# BUCK.net
KiCad netlist of a schematic drawn in Altium Designer
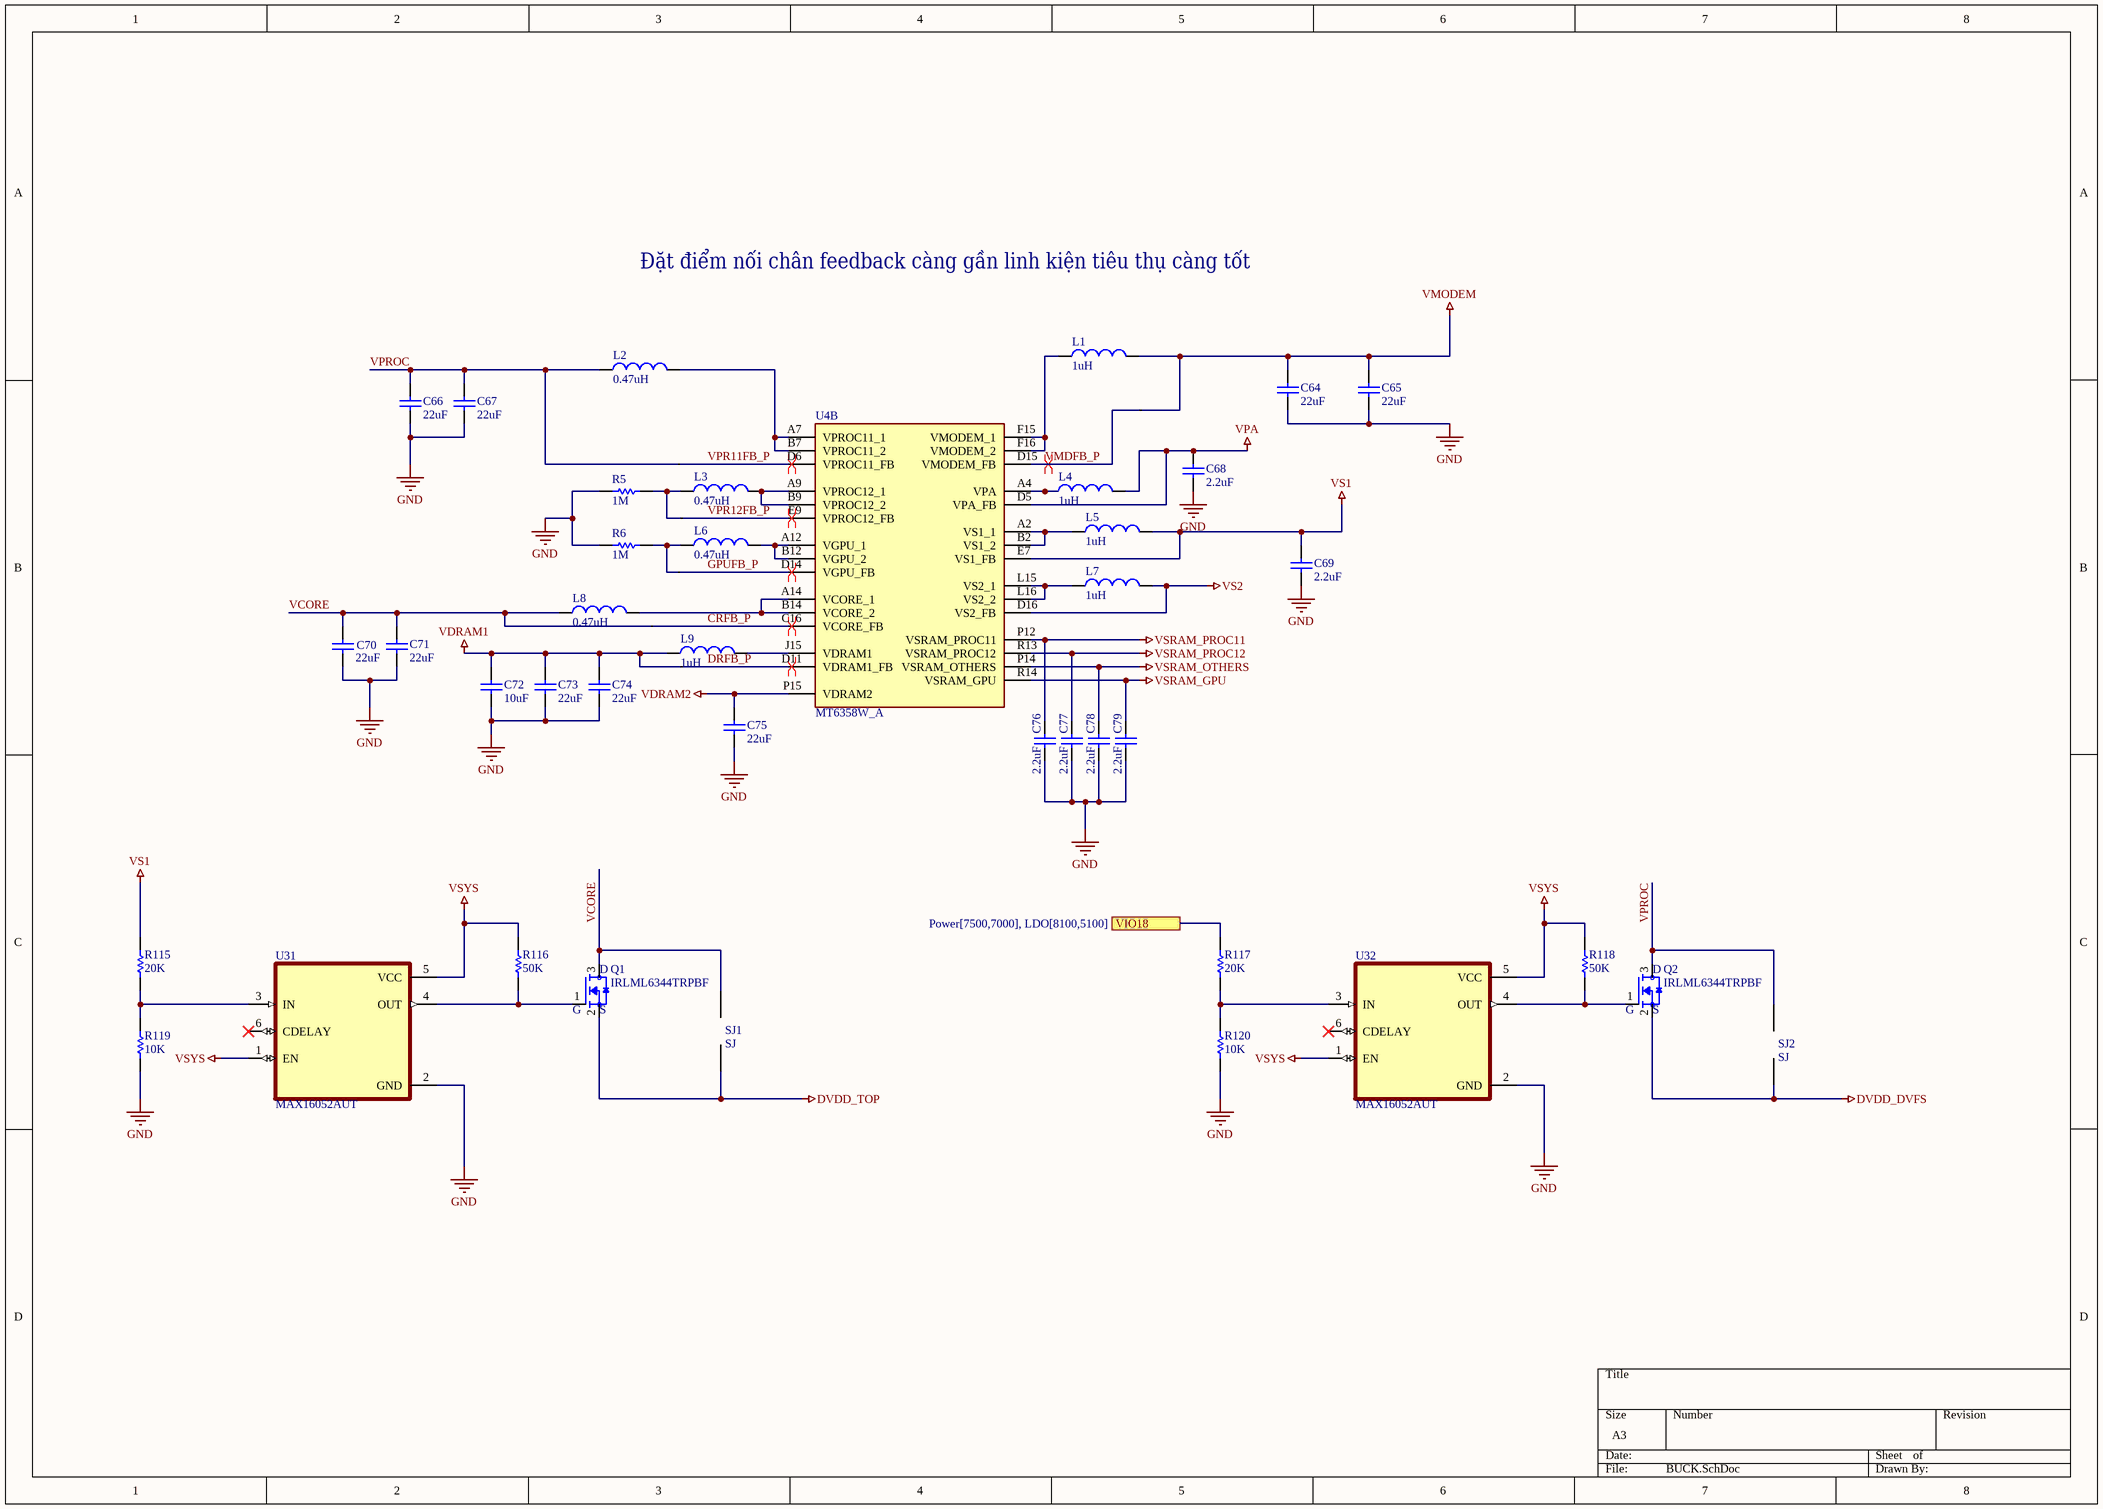
[diagram p0: BUCK.SchDoc]

(export (version "E")
  (design (tool "Eeschema 10.0.6"))
  (components
    (comp (ref ".6") (value "P") (footprint "P") (libsource (lib "kit") (part "P")))
    (comp (ref ".7") (value "P") (footprint "P") (libsource (lib "kit") (part "P")))
    (comp (ref ".9") (value "P") (footprint "P") (libsource (lib "kit") (part "P")))
    (comp (ref ".11") (value "P") (footprint "P") (libsource (lib "kit") (part "P")))
    (comp (ref ".13") (value "P") (footprint "P") (libsource (lib "kit") (part "P")))
    (comp (ref ".14") (value "P") (footprint "P") (libsource (lib "kit") (part "P")))
    (comp (ref "C64")
      (value "22uF")
      (footprint "C1210")
      (fields (field (name "Comment") "C1210"))
      (libsource (lib "kit") (part "C1210"))
    )
    (comp (ref "C65")
      (value "22uF")
      (footprint "C1210")
      (fields (field (name "Comment") "C1210"))
      (libsource (lib "kit") (part "C1210"))
    )
    (comp (ref "C66")
      (value "22uF")
      (footprint "C1210")
      (fields (field (name "Comment") "C1210"))
      (libsource (lib "kit") (part "C1210"))
    )
    (comp (ref "C67")
      (value "22uF")
      (footprint "C1210")
      (fields (field (name "Comment") "C1210"))
      (libsource (lib "kit") (part "C1210"))
    )
    (comp (ref "C68")
      (value "2.2uF")
      (footprint "C0805")
      (fields (field (name "Comment") "C0805"))
      (libsource (lib "kit") (part "C0805"))
    )
    (comp (ref "C69")
      (value "2.2uF")
      (footprint "C0805")
      (fields (field (name "Comment") "C0805"))
      (libsource (lib "kit") (part "C0805"))
    )
    (comp (ref "C70")
      (value "22uF")
      (footprint "C1210")
      (fields (field (name "Comment") "C1210"))
      (libsource (lib "kit") (part "C1210"))
    )
    (comp (ref "C71")
      (value "22uF")
      (footprint "C1210")
      (fields (field (name "Comment") "C1210"))
      (libsource (lib "kit") (part "C1210"))
    )
    (comp (ref "C72")
      (value "10uF")
      (footprint "C1210")
      (fields (field (name "Comment") "C1210"))
      (libsource (lib "kit") (part "C1210"))
    )
    (comp (ref "C73")
      (value "22uF")
      (footprint "C1210")
      (fields (field (name "Comment") "C1210"))
      (libsource (lib "kit") (part "C1210"))
    )
    (comp (ref "C74")
      (value "22uF")
      (footprint "C1210")
      (fields (field (name "Comment") "C1210"))
      (libsource (lib "kit") (part "C1210"))
    )
    (comp (ref "C75")
      (value "22uF")
      (footprint "C1210")
      (fields (field (name "Comment") "C1210"))
      (libsource (lib "kit") (part "C1210"))
    )
    (comp (ref "C76")
      (value "2.2uF")
      (footprint "C0805")
      (fields (field (name "Comment") "C0805"))
      (libsource (lib "kit") (part "C0805"))
    )
    (comp (ref "C77")
      (value "2.2uF")
      (footprint "C0805")
      (fields (field (name "Comment") "C0805"))
      (libsource (lib "kit") (part "C0805"))
    )
    (comp (ref "C78")
      (value "2.2uF")
      (footprint "C0805")
      (fields (field (name "Comment") "C0805"))
      (libsource (lib "kit") (part "C0805"))
    )
    (comp (ref "C79")
      (value "2.2uF")
      (footprint "C0805")
      (fields (field (name "Comment") "C0805"))
      (libsource (lib "kit") (part "C0805"))
    )
    (comp (ref "L1")
      (value "1uH")
      (footprint "L0806")
      (description "Inductor\r\nSMD:1.6x2mm")
      (fields (field (name "Comment") "L0806"))
      (libsource (lib "kit") (part "L0806"))
    )
    (comp (ref "L2")
      (value "0.47uH")
      (footprint "L0806")
      (description "Inductor\r\nSMD:1.6x2mm")
      (fields (field (name "Comment") "L0806"))
      (libsource (lib "kit") (part "L0806"))
    )
    (comp (ref "L3")
      (value "0.47uH")
      (footprint "L0806")
      (description "Inductor\r\nSMD:1.6x2mm")
      (fields (field (name "Comment") "L0806"))
      (libsource (lib "kit") (part "L0806"))
    )
    (comp (ref "L4")
      (value "1uH")
      (footprint "L0806")
      (description "Inductor\r\nSMD:1.6x2mm")
      (fields (field (name "Comment") "L0806"))
      (libsource (lib "kit") (part "L0806"))
    )
    (comp (ref "L5")
      (value "1uH")
      (footprint "L0806")
      (description "Inductor\r\nSMD:1.6x2mm")
      (fields (field (name "Comment") "L0806"))
      (libsource (lib "kit") (part "L0806"))
    )
    (comp (ref "L6")
      (value "0.47uH")
      (footprint "L0806")
      (description "Inductor\r\nSMD:1.6x2mm")
      (fields (field (name "Comment") "L0806"))
      (libsource (lib "kit") (part "L0806"))
    )
    (comp (ref "L7")
      (value "1uH")
      (footprint "L0806")
      (description "Inductor\r\nSMD:1.6x2mm")
      (fields (field (name "Comment") "L0806"))
      (libsource (lib "kit") (part "L0806"))
    )
    (comp (ref "L8")
      (value "0.47uH")
      (footprint "L0806")
      (description "Inductor\r\nSMD:1.6x2mm")
      (fields (field (name "Comment") "L0806"))
      (libsource (lib "kit") (part "L0806"))
    )
    (comp (ref "L9")
      (value "1uH")
      (footprint "L0806")
      (description "Inductor\r\nSMD:1.6x2mm")
      (fields (field (name "Comment") "L0806"))
      (libsource (lib "kit") (part "L0806"))
    )
    (comp (ref "Q1")
      (value "IRLML6344TRPBF")
      (footprint "SOT95P240X112-3N")
      (description "IRLML6344TRPBF N-channel MOSFET Transistor, 5 A, 30 V, 3-Pin SOT-23 ¦ Infineon IRLML6344TRPBF")
      (libsource (lib "kit") (part "IRLML6344TRPBF"))
    )
    (comp (ref "Q2")
      (value "IRLML6344TRPBF")
      (footprint "SOT95P240X112-3N")
      (description "IRLML6344TRPBF N-channel MOSFET Transistor, 5 A, 30 V, 3-Pin SOT-23 ¦ Infineon IRLML6344TRPBF")
      (libsource (lib "kit") (part "IRLML6344TRPBF"))
    )
    (comp (ref "R5")
      (value "1M")
      (footprint "R0603")
      (fields (field (name "Comment") "R0603"))
      (libsource (lib "kit") (part "R0603"))
    )
    (comp (ref "R6")
      (value "1M")
      (footprint "R0603")
      (fields (field (name "Comment") "R0603"))
      (libsource (lib "kit") (part "R0603"))
    )
    (comp (ref "R115")
      (value "20K")
      (footprint "R0603")
      (fields (field (name "Comment") "R0603"))
      (libsource (lib "kit") (part "R0603"))
    )
    (comp (ref "R116")
      (value "50K")
      (footprint "R0603")
      (fields (field (name "Comment") "R0603"))
      (libsource (lib "kit") (part "R0603"))
    )
    (comp (ref "R117")
      (value "20K")
      (footprint "R0603")
      (fields (field (name "Comment") "R0603"))
      (libsource (lib "kit") (part "R0603"))
    )
    (comp (ref "R118")
      (value "50K")
      (footprint "R0603")
      (fields (field (name "Comment") "R0603"))
      (libsource (lib "kit") (part "R0603"))
    )
    (comp (ref "R119")
      (value "10K")
      (footprint "R0603")
      (fields (field (name "Comment") "R0603"))
      (libsource (lib "kit") (part "R0603"))
    )
    (comp (ref "R120")
      (value "10K")
      (footprint "R0603")
      (fields (field (name "Comment") "R0603"))
      (libsource (lib "kit") (part "R0603"))
    )
    (comp (ref "SJ1")
      (value "SJ")
      (footprint "SJ2")
      (description "Để hở. hàn 2 đầu lại nếu cần")
      (libsource (lib "kit") (part "SJ"))
    )
    (comp (ref "SJ2")
      (value "SJ")
      (footprint "SJ2")
      (description "Để hở. hàn 2 đầu lại nếu cần")
      (libsource (lib "kit") (part "SJ"))
    )
    (comp (ref "U4")
      (value "MT6358W_A")
      (footprint "BGA194C40P16X15_640X600X66")
      (description "Integrated Circuit")
      (fields
        (field (name "MANUFACTURER_PART_NUMBER") "MT6358W/A")
        (field (name "MOUSER PART NUMBER") "840-MT6358W/A")
      )
      (libsource (lib "kit") (part "MT6358W_A"))
    )
    (comp (ref "U31")
      (value "MAX16052AUT")
      (footprint "SOT95P280X145-6N")
      (description "High-Voltage, Adjustable Sequencing/Supervisory Circuitss")
      (libsource (lib "kit") (part "MAX16052AUT"))
    )
    (comp (ref "U32")
      (value "MAX16052AUT")
      (footprint "SOT95P280X145-6N")
      (description "High-Voltage, Adjustable Sequencing/Supervisory Circuitss")
      (libsource (lib "kit") (part "MAX16052AUT"))
    )
  )
  (nets
    (net (code "1") (name "/CRFB_P") (class "Default")
      (node (ref ".13") (pin "2") (pinfunction "2_2") (pintype "passive"))
      (node (ref "U4") (pin "C16") (pinfunction "VCORE_FB_C16") (pintype "passive"))
    )
    (net (code "2") (name "/DRFB_P") (class "Default")
      (node (ref ".14") (pin "2") (pinfunction "2_2") (pintype "passive"))
      (node (ref "U4") (pin "D11") (pinfunction "VDRAM1_FB_D11") (pintype "passive"))
    )
    (net (code "3") (name "/GPUFB_P") (class "Default")
      (node (ref ".11") (pin "2") (pinfunction "2_2") (pintype "passive"))
      (node (ref "U4") (pin "D14") (pinfunction "VGPU_FB_D14") (pintype "passive"))
    )
    (net (code "4") (name "/VCORE") (class "Default")
      (node (ref ".13") (pin "1") (pinfunction "1_1") (pintype "passive"))
      (node (ref "C70") (pin "2") (pinfunction "2_2") (pintype "passive"))
      (node (ref "C71") (pin "2") (pinfunction "2_2") (pintype "passive"))
      (node (ref "L8") (pin "1") (pinfunction "1_1") (pintype "passive"))
      (node (ref "Q1") (pin "3") (pinfunction "D_3") (pintype "passive"))
      (node (ref "SJ1") (pin "2") (pinfunction "2_2") (pintype "passive"))
    )
    (net (code "5") (name "/VIO18") (class "Default")
      (node (ref "R117") (pin "2") (pinfunction "2_2") (pintype "passive"))
    )
    (net (code "6") (name "/VMDFB_P") (class "Default")
      (node (ref ".6") (pin "1") (pinfunction "1_1") (pintype "passive"))
      (node (ref "U4") (pin "D15") (pinfunction "VMODEM_FB_D15") (pintype "passive"))
    )
    (net (code "7") (name "/VPR11FB_P") (class "Default")
      (node (ref ".7") (pin "2") (pinfunction "2_2") (pintype "passive"))
      (node (ref "U4") (pin "D6") (pinfunction "VPROC11_FB_D6") (pintype "passive"))
    )
    (net (code "8") (name "/VPR12FB_P") (class "Default")
      (node (ref ".9") (pin "2") (pinfunction "2_2") (pintype "passive"))
      (node (ref "U4") (pin "E9") (pinfunction "VPROC12_FB_E9") (pintype "passive"))
    )
    (net (code "9") (name "/VPROC") (class "Default")
      (node (ref ".7") (pin "1") (pinfunction "1_1") (pintype "passive"))
      (node (ref "C66") (pin "2") (pinfunction "2_2") (pintype "passive"))
      (node (ref "C67") (pin "2") (pinfunction "2_2") (pintype "passive"))
      (node (ref "L2") (pin "1") (pinfunction "1_1") (pintype "passive"))
      (node (ref "Q2") (pin "3") (pinfunction "D_3") (pintype "passive"))
      (node (ref "SJ2") (pin "2") (pinfunction "2_2") (pintype "passive"))
    )
    (net (code "10") (name "DVDD_DVFS") (class "Default")
      (node (ref "Q2") (pin "2") (pinfunction "S_2") (pintype "passive"))
      (node (ref "SJ2") (pin "1") (pinfunction "1_1") (pintype "passive"))
    )
    (net (code "11") (name "DVDD_TOP") (class "Default")
      (node (ref "Q1") (pin "2") (pinfunction "S_2") (pintype "passive"))
      (node (ref "SJ1") (pin "1") (pinfunction "1_1") (pintype "passive"))
    )
    (net (code "12") (name "GND") (class "Default")
      (node (ref "C64") (pin "1") (pinfunction "1_1") (pintype "passive"))
      (node (ref "C65") (pin "1") (pinfunction "1_1") (pintype "passive"))
      (node (ref "C66") (pin "1") (pinfunction "1_1") (pintype "passive"))
      (node (ref "C67") (pin "1") (pinfunction "1_1") (pintype "passive"))
      (node (ref "C68") (pin "1") (pinfunction "1_1") (pintype "passive"))
      (node (ref "C69") (pin "1") (pinfunction "1_1") (pintype "passive"))
      (node (ref "C70") (pin "1") (pinfunction "1_1") (pintype "passive"))
      (node (ref "C71") (pin "1") (pinfunction "1_1") (pintype "passive"))
      (node (ref "C72") (pin "1") (pinfunction "1_1") (pintype "passive"))
      (node (ref "C73") (pin "1") (pinfunction "1_1") (pintype "passive"))
      (node (ref "C74") (pin "1") (pinfunction "1_1") (pintype "passive"))
      (node (ref "C75") (pin "1") (pinfunction "1_1") (pintype "passive"))
      (node (ref "C76") (pin "1") (pinfunction "1_1") (pintype "passive"))
      (node (ref "C77") (pin "1") (pinfunction "1_1") (pintype "passive"))
      (node (ref "C78") (pin "1") (pinfunction "1_1") (pintype "passive"))
      (node (ref "C79") (pin "1") (pinfunction "1_1") (pintype "passive"))
      (node (ref "R119") (pin "1") (pinfunction "1_1") (pintype "passive"))
      (node (ref "R120") (pin "1") (pinfunction "1_1") (pintype "passive"))
      (node (ref "R5") (pin "1") (pinfunction "1_1") (pintype "passive"))
      (node (ref "R6") (pin "1") (pinfunction "1_1") (pintype "passive"))
      (node (ref "U31") (pin "2") (pinfunction "GND_2") (pintype "power_in"))
      (node (ref "U32") (pin "2") (pinfunction "GND_2") (pintype "power_in"))
    )
    (net (code "13") (name "Net-(.9-Pad1)") (class "Default")
      (node (ref ".9") (pin "1") (pinfunction "1_1") (pintype "passive"))
      (node (ref "L3") (pin "1") (pinfunction "1_1") (pintype "passive"))
      (node (ref "R5") (pin "2") (pinfunction "2_2") (pintype "passive"))
    )
    (net (code "14") (name "Net-(.11-Pad1)") (class "Default")
      (node (ref ".11") (pin "1") (pinfunction "1_1") (pintype "passive"))
      (node (ref "L6") (pin "1") (pinfunction "1_1") (pintype "passive"))
      (node (ref "R6") (pin "2") (pinfunction "2_2") (pintype "passive"))
    )
    (net (code "15") (name "Net-(Q1-G)") (class "Default")
      (node (ref "Q1") (pin "1") (pinfunction "G_1") (pintype "passive"))
      (node (ref "R116") (pin "1") (pinfunction "1_1") (pintype "passive"))
      (node (ref "U31") (pin "4") (pinfunction "OUT_4") (pintype "output"))
    )
    (net (code "16") (name "Net-(Q2-G)") (class "Default")
      (node (ref "Q2") (pin "1") (pinfunction "G_1") (pintype "passive"))
      (node (ref "R118") (pin "1") (pinfunction "1_1") (pintype "passive"))
      (node (ref "U32") (pin "4") (pinfunction "OUT_4") (pintype "output"))
    )
    (net (code "17") (name "Net-(U4B-VCORE_1)") (class "Default")
      (node (ref "L8") (pin "2") (pinfunction "2_2") (pintype "passive"))
      (node (ref "U4") (pin "A14") (pinfunction "VCORE_1_A14") (pintype "passive"))
      (node (ref "U4") (pin "B14") (pinfunction "VCORE_2_B14") (pintype "passive"))
    )
    (net (code "18") (name "Net-(U4B-VDRAM1)") (class "Default")
      (node (ref "L9") (pin "2") (pinfunction "2_2") (pintype "passive"))
      (node (ref "U4") (pin "J15") (pinfunction "VDRAM1_J15") (pintype "passive"))
    )
    (net (code "19") (name "Net-(U4B-VGPU_1)") (class "Default")
      (node (ref "L6") (pin "2") (pinfunction "2_2") (pintype "passive"))
      (node (ref "U4") (pin "A12") (pinfunction "VGPU_1_A12") (pintype "passive"))
      (node (ref "U4") (pin "B12") (pinfunction "VGPU_2_B12") (pintype "passive"))
    )
    (net (code "20") (name "Net-(U4B-VMODEM_1)") (class "Default")
      (node (ref "L1") (pin "1") (pinfunction "1_1") (pintype "passive"))
      (node (ref "U4") (pin "F15") (pinfunction "VMODEM_1_F15") (pintype "passive"))
      (node (ref "U4") (pin "F16") (pinfunction "VMODEM_2_F16") (pintype "passive"))
    )
    (net (code "21") (name "Net-(U4B-VPA)") (class "Default")
      (node (ref "L4") (pin "1") (pinfunction "1_1") (pintype "passive"))
      (node (ref "U4") (pin "A4") (pinfunction "VPA_A4") (pintype "passive"))
    )
    (net (code "22") (name "Net-(U4B-VPROC11_1)") (class "Default")
      (node (ref "L2") (pin "2") (pinfunction "2_2") (pintype "passive"))
      (node (ref "U4") (pin "A7") (pinfunction "VPROC11_1_A7") (pintype "passive"))
      (node (ref "U4") (pin "B7") (pinfunction "VPROC11_2_B7") (pintype "passive"))
    )
    (net (code "23") (name "Net-(U4B-VPROC12_1)") (class "Default")
      (node (ref "L3") (pin "2") (pinfunction "2_2") (pintype "passive"))
      (node (ref "U4") (pin "A9") (pinfunction "VPROC12_1_A9") (pintype "passive"))
      (node (ref "U4") (pin "B9") (pinfunction "VPROC12_2_B9") (pintype "passive"))
    )
    (net (code "24") (name "Net-(U4B-VS1_1)") (class "Default")
      (node (ref "L5") (pin "1") (pinfunction "1_1") (pintype "passive"))
      (node (ref "U4") (pin "A2") (pinfunction "VS1_1_A2") (pintype "passive"))
      (node (ref "U4") (pin "B2") (pinfunction "VS1_2_B2") (pintype "passive"))
    )
    (net (code "25") (name "Net-(U4B-VS2_1)") (class "Default")
      (node (ref "L7") (pin "1") (pinfunction "1_1") (pintype "passive"))
      (node (ref "U4") (pin "L15") (pinfunction "VS2_1_L15") (pintype "passive"))
      (node (ref "U4") (pin "L16") (pinfunction "VS2_2_L16") (pintype "passive"))
    )
    (net (code "26") (name "Net-(U31-IN)") (class "Default")
      (node (ref "R115") (pin "1") (pinfunction "1_1") (pintype "passive"))
      (node (ref "R119") (pin "2") (pinfunction "2_2") (pintype "passive"))
      (node (ref "U31") (pin "3") (pinfunction "IN_3") (pintype "input"))
    )
    (net (code "27") (name "Net-(U32-IN)") (class "Default")
      (node (ref "R117") (pin "1") (pinfunction "1_1") (pintype "passive"))
      (node (ref "R120") (pin "2") (pinfunction "2_2") (pintype "passive"))
      (node (ref "U32") (pin "3") (pinfunction "IN_3") (pintype "input"))
    )
    (net (code "28") (name "VDRAM1") (class "Default")
      (node (ref ".14") (pin "1") (pinfunction "1_1") (pintype "passive"))
      (node (ref "C72") (pin "2") (pinfunction "2_2") (pintype "passive"))
      (node (ref "C73") (pin "2") (pinfunction "2_2") (pintype "passive"))
      (node (ref "C74") (pin "2") (pinfunction "2_2") (pintype "passive"))
      (node (ref "L9") (pin "1") (pinfunction "1_1") (pintype "passive"))
    )
    (net (code "29") (name "VDRAM2") (class "Default")
      (node (ref "C75") (pin "2") (pinfunction "2_2") (pintype "passive"))
      (node (ref "U4") (pin "P15") (pinfunction "VDRAM2_P15") (pintype "passive"))
    )
    (net (code "30") (name "VMODEM") (class "Default")
      (node (ref ".6") (pin "2") (pinfunction "2_2") (pintype "passive"))
      (node (ref "C64") (pin "2") (pinfunction "2_2") (pintype "passive"))
      (node (ref "C65") (pin "2") (pinfunction "2_2") (pintype "passive"))
      (node (ref "L1") (pin "2") (pinfunction "2_2") (pintype "passive"))
    )
    (net (code "31") (name "VPA") (class "Default")
      (node (ref "C68") (pin "2") (pinfunction "2_2") (pintype "passive"))
      (node (ref "L4") (pin "2") (pinfunction "2_2") (pintype "passive"))
      (node (ref "U4") (pin "D5") (pinfunction "VPA_FB_D5") (pintype "passive"))
    )
    (net (code "32") (name "VS1") (class "Default")
      (node (ref "C69") (pin "2") (pinfunction "2_2") (pintype "passive"))
      (node (ref "L5") (pin "2") (pinfunction "2_2") (pintype "passive"))
      (node (ref "R115") (pin "2") (pinfunction "2_2") (pintype "passive"))
      (node (ref "U4") (pin "E7") (pinfunction "VS1_FB_E7") (pintype "passive"))
    )
    (net (code "33") (name "VS2") (class "Default")
      (node (ref "L7") (pin "2") (pinfunction "2_2") (pintype "passive"))
      (node (ref "U4") (pin "D16") (pinfunction "VS2_FB_D16") (pintype "passive"))
    )
    (net (code "34") (name "VSRAM_GPU") (class "Default")
      (node (ref "C79") (pin "2") (pinfunction "2_2") (pintype "passive"))
      (node (ref "U4") (pin "R14") (pinfunction "VSRAM_GPU_R14") (pintype "passive"))
    )
    (net (code "35") (name "VSRAM_OTHERS") (class "Default")
      (node (ref "C78") (pin "2") (pinfunction "2_2") (pintype "passive"))
      (node (ref "U4") (pin "P14") (pinfunction "VSRAM_OTHERS_P14") (pintype "passive"))
    )
    (net (code "36") (name "VSRAM_PROC11") (class "Default")
      (node (ref "C76") (pin "2") (pinfunction "2_2") (pintype "passive"))
      (node (ref "U4") (pin "P12") (pinfunction "VSRAM_PROC11_P12") (pintype "passive"))
    )
    (net (code "37") (name "VSRAM_PROC12") (class "Default")
      (node (ref "C77") (pin "2") (pinfunction "2_2") (pintype "passive"))
      (node (ref "U4") (pin "R13") (pinfunction "VSRAM_PROC12_R13") (pintype "passive"))
    )
    (net (code "38") (name "VSYS") (class "Default")
      (node (ref "R116") (pin "2") (pinfunction "2_2") (pintype "passive"))
      (node (ref "R118") (pin "2") (pinfunction "2_2") (pintype "passive"))
      (node (ref "U31") (pin "1") (pinfunction "EN_1") (pintype "bidirectional"))
      (node (ref "U31") (pin "5") (pinfunction "VCC_5") (pintype "power_in"))
      (node (ref "U32") (pin "1") (pinfunction "EN_1") (pintype "bidirectional"))
      (node (ref "U32") (pin "5") (pinfunction "VCC_5") (pintype "power_in"))
    )
    (net (code "39") (name "unconnected-(U31-CDELAY-Pad6)") (class "Default")
      (node (ref "U31") (pin "6") (pinfunction "CDELAY_6") (pintype "bidirectional+no_connect"))
    )
    (net (code "40") (name "unconnected-(U32-CDELAY-Pad6)") (class "Default")
      (node (ref "U32") (pin "6") (pinfunction "CDELAY_6") (pintype "bidirectional+no_connect"))
    )
  )
)
